# FPGA_IO.net
KiCad netlist of a schematic drawn in Altium Designer
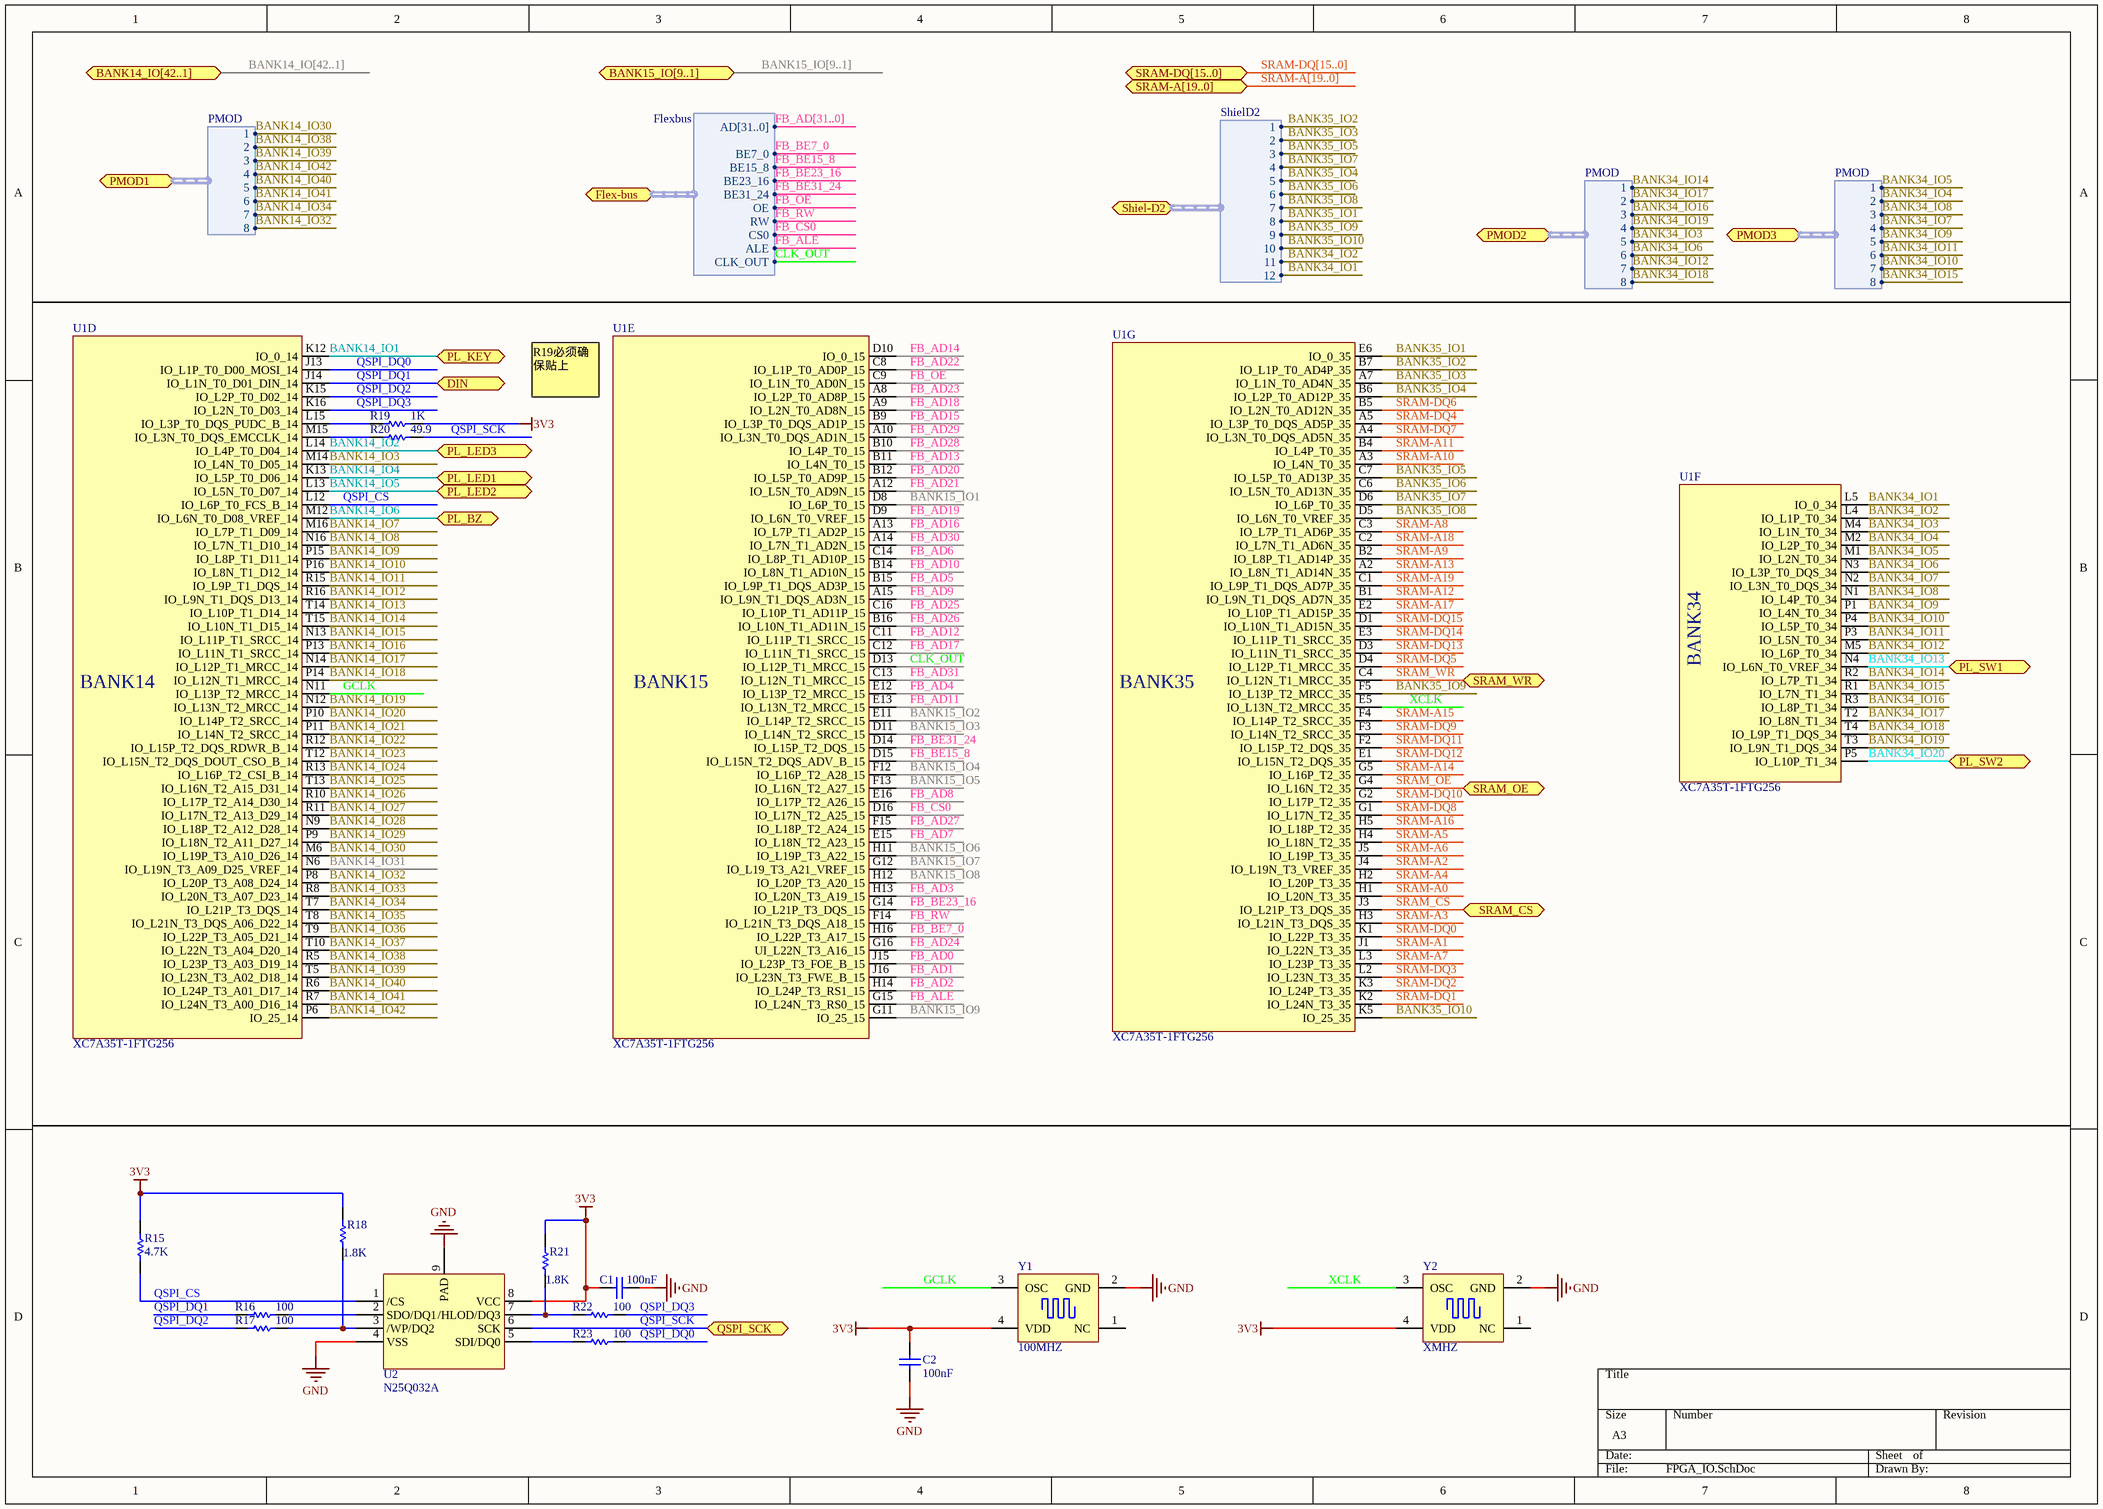
[diagram p0: FPGA_IO.SchDoc]

(export (version "E")
  (design (tool "Eeschema 10.0.6"))
  (components
    (comp (ref "C1")
      (value "100nF")
      (footprint "1608[0603]")
      (description "贴片电容")
      (fields (field (name "Comment") "Cap") (field (name "PUBLISHER") "Altium Limited"))
      (libsource (lib "Sparks") (part "Cap"))
    )
    (comp (ref "C2")
      (value "100nF")
      (footprint "1608[0603]")
      (description "贴片电容")
      (fields (field (name "Comment") "Cap") (field (name "PUBLISHER") "Altium Limited"))
      (libsource (lib "Sparks") (part "Cap"))
    )
    (comp (ref "R15")
      (value "4.7K")
      (footprint "1608[0603]")
      (description "贴片电阻")
      (fields (field (name "Comment") "Res") (field (name "PUBLISHER") "Altium Limited"))
      (libsource (lib "Sparks") (part "Res"))
    )
    (comp (ref "R16")
      (value "100")
      (footprint "1608[0603]")
      (description "贴片电阻")
      (fields (field (name "Comment") "Res") (field (name "PUBLISHER") "Altium Limited"))
      (libsource (lib "Sparks") (part "Res"))
    )
    (comp (ref "R17")
      (value "100")
      (footprint "1608[0603]")
      (description "贴片电阻")
      (fields (field (name "Comment") "Res") (field (name "PUBLISHER") "Altium Limited"))
      (libsource (lib "Sparks") (part "Res"))
    )
    (comp (ref "R18")
      (value "1.8K")
      (footprint "1608[0603]")
      (description "贴片电阻")
      (fields (field (name "Comment") "Res") (field (name "PUBLISHER") "Altium Limited"))
      (libsource (lib "Sparks") (part "Res"))
    )
    (comp (ref "R19")
      (value "1K")
      (footprint "1608[0603]")
      (description "贴片电阻")
      (fields (field (name "Comment") "Res") (field (name "PUBLISHER") "Altium Limited"))
      (libsource (lib "Sparks") (part "Res"))
    )
    (comp (ref "R20")
      (value "49.9")
      (footprint "R2012")
      (description "贴片电阻")
      (fields (field (name "Comment") "Res") (field (name "PUBLISHER") "Altium Limited"))
      (libsource (lib "Sparks") (part "Res"))
    )
    (comp (ref "R21")
      (value "1.8K")
      (footprint "1608[0603]")
      (description "贴片电阻")
      (fields (field (name "Comment") "Res") (field (name "PUBLISHER") "Altium Limited"))
      (libsource (lib "Sparks") (part "Res"))
    )
    (comp (ref "R22")
      (value "100")
      (footprint "1608[0603]")
      (description "贴片电阻")
      (fields (field (name "Comment") "Res") (field (name "PUBLISHER") "Altium Limited"))
      (libsource (lib "Sparks") (part "Res"))
    )
    (comp (ref "R23")
      (value "100")
      (footprint "R2012")
      (description "贴片电阻")
      (fields (field (name "Comment") "Res") (field (name "PUBLISHER") "Altium Limited"))
      (libsource (lib "Sparks") (part "Res"))
    )
    (comp (ref "U1")
      (value "XC7A35T-1FTG256")
      (footprint "BGA100P9X9-81A")
      (libsource (lib "Schlib") (part "XC7A35T-1FTG256"))
    )
    (comp (ref "U2")
      (value "N25Q032A")
      (footprint "QFN127P500X600X100_HS-9N")
      (libsource (lib "2号库") (part "N25Q032A"))
    )
    (comp (ref "Y1") (value "100MHZ") (footprint "XTAL7_3225") (libsource (lib "K60-V4.0") (part "XTAL1")))
    (comp (ref "Y2") (value "XMHZ") (footprint "XTAL7_3225") (libsource (lib "K60-V4.0") (part "XTAL1")))
  )
  (nets
    (net (code "4") (name "/BANK14_IO1") (class "Default")
      (node (ref "U1") (pin "K12") (pinfunction "IO_0_14_K12") (pintype "passive"))
    )
    (net (code "5") (name "/BANK14_IO2") (class "Default")
      (node (ref "U1") (pin "L14") (pinfunction "IO_L4P_T0_D04_14_L14") (pintype "passive"))
    )
    (net (code "6") (name "/BANK14_IO3") (class "Default")
      (node (ref "U1") (pin "M14") (pinfunction "IO_L4N_T0_D05_14_M14") (pintype "passive"))
    )
    (net (code "7") (name "/BANK14_IO4") (class "Default")
      (node (ref "U1") (pin "K13") (pinfunction "IO_L5P_T0_D06_14_K13") (pintype "passive"))
    )
    (net (code "8") (name "/BANK14_IO5") (class "Default")
      (node (ref "U1") (pin "L13") (pinfunction "IO_L5N_T0_D07_14_L13") (pintype "passive"))
    )
    (net (code "9") (name "/BANK14_IO6") (class "Default")
      (node (ref "U1") (pin "M12") (pinfunction "IO_L6N_T0_D08_VREF_14_M12") (pintype "passive"))
    )
    (net (code "10") (name "/BANK14_IO7") (class "Default")
      (node (ref "U1") (pin "M16") (pinfunction "IO_L7P_T1_D09_14_M16") (pintype "passive"))
    )
    (net (code "11") (name "/BANK14_IO8") (class "Default")
      (node (ref "U1") (pin "N16") (pinfunction "IO_L7N_T1_D10_14_N16") (pintype "passive"))
    )
    (net (code "12") (name "/BANK14_IO9") (class "Default")
      (node (ref "U1") (pin "P15") (pinfunction "IO_L8P_T1_D11_14_P15") (pintype "passive"))
    )
    (net (code "13") (name "/BANK14_IO10") (class "Default")
      (node (ref "U1") (pin "P16") (pinfunction "IO_L8N_T1_D12_14_P16") (pintype "passive"))
    )
    (net (code "14") (name "/BANK14_IO11") (class "Default")
      (node (ref "U1") (pin "R15") (pinfunction "IO_L9P_T1_DQS_14_R15") (pintype "passive"))
    )
    (net (code "15") (name "/BANK14_IO12") (class "Default")
      (node (ref "U1") (pin "R16") (pinfunction "IO_L9N_T1_DQS_D13_14_R16") (pintype "passive"))
    )
    (net (code "16") (name "/BANK14_IO13") (class "Default")
      (node (ref "U1") (pin "T14") (pinfunction "IO_L10P_T1_D14_14_T14") (pintype "passive"))
    )
    (net (code "17") (name "/BANK14_IO14") (class "Default")
      (node (ref "U1") (pin "T15") (pinfunction "IO_L10N_T1_D15_14_T15") (pintype "passive"))
    )
    (net (code "18") (name "/BANK14_IO15") (class "Default")
      (node (ref "U1") (pin "N13") (pinfunction "IO_L11P_T1_SRCC_14_N13") (pintype "passive"))
    )
    (net (code "19") (name "/BANK14_IO16") (class "Default")
      (node (ref "U1") (pin "P13") (pinfunction "IO_L11N_T1_SRCC_14_P13") (pintype "passive"))
    )
    (net (code "20") (name "/BANK14_IO17") (class "Default")
      (node (ref "U1") (pin "N14") (pinfunction "IO_L12P_T1_MRCC_14_N14") (pintype "passive"))
    )
    (net (code "21") (name "/BANK14_IO18") (class "Default")
      (node (ref "U1") (pin "P14") (pinfunction "IO_L12N_T1_MRCC_14_P14") (pintype "passive"))
    )
    (net (code "22") (name "/BANK14_IO19") (class "Default")
      (node (ref "U1") (pin "N12") (pinfunction "IO_L13N_T2_MRCC_14_N12") (pintype "passive"))
    )
    (net (code "23") (name "/BANK14_IO20") (class "Default")
      (node (ref "U1") (pin "P10") (pinfunction "IO_L14P_T2_SRCC_14_P10") (pintype "passive"))
    )
    (net (code "24") (name "/BANK14_IO21") (class "Default")
      (node (ref "U1") (pin "P11") (pinfunction "IO_L14N_T2_SRCC_14_P11") (pintype "passive"))
    )
    (net (code "25") (name "/BANK14_IO22") (class "Default")
      (node (ref "U1") (pin "R12") (pinfunction "IO_L15P_T2_DQS_RDWR_B_14_R12") (pintype "passive"))
    )
    (net (code "26") (name "/BANK14_IO23") (class "Default")
      (node (ref "U1") (pin "T12") (pinfunction "IO_L15N_T2_DQS_DOUT_CSO_B_14_T12") (pintype "passive"))
    )
    (net (code "27") (name "/BANK14_IO24") (class "Default")
      (node (ref "U1") (pin "R13") (pinfunction "IO_L16P_T2_CSI_B_14_R13") (pintype "passive"))
    )
    (net (code "28") (name "/BANK14_IO25") (class "Default")
      (node (ref "U1") (pin "T13") (pinfunction "IO_L16N_T2_A15_D31_14_T13") (pintype "passive"))
    )
    (net (code "29") (name "/BANK14_IO26") (class "Default")
      (node (ref "U1") (pin "R10") (pinfunction "IO_L17P_T2_A14_D30_14_R10") (pintype "passive"))
    )
    (net (code "30") (name "/BANK14_IO27") (class "Default")
      (node (ref "U1") (pin "R11") (pinfunction "IO_L17N_T2_A13_D29_14_R11") (pintype "passive"))
    )
    (net (code "31") (name "/BANK14_IO28") (class "Default")
      (node (ref "U1") (pin "N9") (pinfunction "IO_L18P_T2_A12_D28_14_N9") (pintype "passive"))
    )
    (net (code "32") (name "/BANK14_IO29") (class "Default")
      (node (ref "U1") (pin "P9") (pinfunction "IO_L18N_T2_A11_D27_14_P9") (pintype "passive"))
    )
    (net (code "33") (name "/BANK14_IO30") (class "Default")
      (node (ref "U1") (pin "M6") (pinfunction "IO_L19P_T3_A10_D26_14_M6") (pintype "passive"))
    )
    (net (code "34") (name "/BANK14_IO31") (class "Default")
      (node (ref "U1") (pin "N6") (pinfunction "IO_L19N_T3_A09_D25_VREF_14_N6") (pintype "passive"))
    )
    (net (code "35") (name "/BANK14_IO32") (class "Default")
      (node (ref "U1") (pin "P8") (pinfunction "IO_L20P_T3_A08_D24_14_P8") (pintype "passive"))
    )
    (net (code "36") (name "/BANK14_IO33") (class "Default")
      (node (ref "U1") (pin "R8") (pinfunction "IO_L20N_T3_A07_D23_14_R8") (pintype "passive"))
    )
    (net (code "37") (name "/BANK14_IO34") (class "Default")
      (node (ref "U1") (pin "T7") (pinfunction "IO_L21P_T3_DQS_14_T7") (pintype "passive"))
    )
    (net (code "38") (name "/BANK14_IO35") (class "Default")
      (node (ref "U1") (pin "T8") (pinfunction "IO_L21N_T3_DQS_A06_D22_14_T8") (pintype "passive"))
    )
    (net (code "39") (name "/BANK14_IO36") (class "Default")
      (node (ref "U1") (pin "T9") (pinfunction "IO_L22P_T3_A05_D21_14_T9") (pintype "passive"))
    )
    (net (code "40") (name "/BANK14_IO37") (class "Default")
      (node (ref "U1") (pin "T10") (pinfunction "IO_L22N_T3_A04_D20_14_T10") (pintype "passive"))
    )
    (net (code "41") (name "/BANK14_IO38") (class "Default")
      (node (ref "U1") (pin "R5") (pinfunction "IO_L23P_T3_A03_D19_14_R5") (pintype "passive"))
    )
    (net (code "42") (name "/BANK14_IO39") (class "Default")
      (node (ref "U1") (pin "T5") (pinfunction "IO_L23N_T3_A02_D18_14_T5") (pintype "passive"))
    )
    (net (code "43") (name "/BANK14_IO40") (class "Default")
      (node (ref "U1") (pin "R6") (pinfunction "IO_L24P_T3_A01_D17_14_R6") (pintype "passive"))
    )
    (net (code "44") (name "/BANK14_IO41") (class "Default")
      (node (ref "U1") (pin "R7") (pinfunction "IO_L24N_T3_A00_D16_14_R7") (pintype "passive"))
    )
    (net (code "45") (name "/BANK14_IO42") (class "Default")
      (node (ref "U1") (pin "P6") (pinfunction "IO_25_14_P6") (pintype "passive"))
    )
    (net (code "47") (name "/BANK15_IO1") (class "Default")
      (node (ref "U1") (pin "D8") (pinfunction "IO_L6P_T0_15_D8") (pintype "passive"))
    )
    (net (code "48") (name "/BANK15_IO2") (class "Default")
      (node (ref "U1") (pin "E11") (pinfunction "IO_L14P_T2_SRCC_15_E11") (pintype "passive"))
    )
    (net (code "49") (name "/BANK15_IO3") (class "Default")
      (node (ref "U1") (pin "D11") (pinfunction "IO_L14N_T2_SRCC_15_D11") (pintype "passive"))
    )
    (net (code "50") (name "/BANK15_IO4") (class "Default")
      (node (ref "U1") (pin "F12") (pinfunction "IO_L16P_T2_A28_15_F12") (pintype "passive"))
    )
    (net (code "51") (name "/BANK15_IO5") (class "Default")
      (node (ref "U1") (pin "F13") (pinfunction "IO_L16N_T2_A27_15_F13") (pintype "passive"))
    )
    (net (code "52") (name "/BANK15_IO6") (class "Default")
      (node (ref "U1") (pin "H11") (pinfunction "IO_L19P_T3_A22_15_H11") (pintype "passive"))
    )
    (net (code "53") (name "/BANK15_IO7") (class "Default")
      (node (ref "U1") (pin "G12") (pinfunction "IO_L19_T3_A21_VREF_15_G12") (pintype "passive"))
    )
    (net (code "54") (name "/BANK15_IO8") (class "Default")
      (node (ref "U1") (pin "H12") (pinfunction "IO_L20P_T3_A20_15_H12") (pintype "passive"))
    )
    (net (code "55") (name "/BANK15_IO9") (class "Default")
      (node (ref "U1") (pin "G11") (pinfunction "IO_25_15_G11") (pintype "passive"))
    )
    (net (code "57") (name "/BANK34_IO1") (class "Default")
      (node (ref "U1") (pin "L5") (pinfunction "IO_0_34_L5") (pintype "passive"))
    )
    (net (code "58") (name "/BANK34_IO2") (class "Default")
      (node (ref "U1") (pin "L4") (pinfunction "IO_L1P_T0_34_L4") (pintype "passive"))
    )
    (net (code "59") (name "/BANK34_IO3") (class "Default")
      (node (ref "U1") (pin "M4") (pinfunction "IO_L1N_T0_34_M4") (pintype "passive"))
    )
    (net (code "60") (name "/BANK34_IO4") (class "Default")
      (node (ref "U1") (pin "M2") (pinfunction "IO_L2P_T0_34_M2") (pintype "passive"))
    )
    (net (code "61") (name "/BANK34_IO5") (class "Default")
      (node (ref "U1") (pin "M1") (pinfunction "IO_L2N_T0_34_M1") (pintype "passive"))
    )
    (net (code "62") (name "/BANK34_IO6") (class "Default")
      (node (ref "U1") (pin "N3") (pinfunction "IO_L3P_T0_DQS_34_N3") (pintype "passive"))
    )
    (net (code "63") (name "/BANK34_IO7") (class "Default")
      (node (ref "U1") (pin "N2") (pinfunction "IO_L3N_T0_DQS_34_N2") (pintype "passive"))
    )
    (net (code "64") (name "/BANK34_IO8") (class "Default")
      (node (ref "U1") (pin "N1") (pinfunction "IO_L4P_T0_34_N1") (pintype "passive"))
    )
    (net (code "65") (name "/BANK34_IO9") (class "Default")
      (node (ref "U1") (pin "P1") (pinfunction "IO_L4N_T0_34_P1") (pintype "passive"))
    )
    (net (code "66") (name "/BANK34_IO10") (class "Default")
      (node (ref "U1") (pin "P4") (pinfunction "IO_L5P_T0_34_P4") (pintype "passive"))
    )
    (net (code "67") (name "/BANK34_IO11") (class "Default")
      (node (ref "U1") (pin "P3") (pinfunction "IO_L5N_T0_34_P3") (pintype "passive"))
    )
    (net (code "68") (name "/BANK34_IO12") (class "Default")
      (node (ref "U1") (pin "M5") (pinfunction "IO_L6P_T0_34_M5") (pintype "passive"))
    )
    (net (code "69") (name "/BANK34_IO13") (class "Default")
      (node (ref "U1") (pin "N4") (pinfunction "IO_L6N_T0_VREF_34_N4") (pintype "passive"))
    )
    (net (code "70") (name "/BANK34_IO14") (class "Default")
      (node (ref "U1") (pin "R2") (pinfunction "IO_L7P_T1_34_R2") (pintype "passive"))
    )
    (net (code "71") (name "/BANK34_IO15") (class "Default")
      (node (ref "U1") (pin "R1") (pinfunction "IO_L7N_T1_34_R1") (pintype "passive"))
    )
    (net (code "72") (name "/BANK34_IO16") (class "Default")
      (node (ref "U1") (pin "R3") (pinfunction "IO_L8P_T1_34_R3") (pintype "passive"))
    )
    (net (code "73") (name "/BANK34_IO17") (class "Default")
      (node (ref "U1") (pin "T2") (pinfunction "IO_L8N_T1_34_T2") (pintype "passive"))
    )
    (net (code "74") (name "/BANK34_IO18") (class "Default")
      (node (ref "U1") (pin "T4") (pinfunction "IO_L9P_T1_DQS_34_T4") (pintype "passive"))
    )
    (net (code "75") (name "/BANK34_IO19") (class "Default")
      (node (ref "U1") (pin "T3") (pinfunction "IO_L9N_T1_DQS_34_T3") (pintype "passive"))
    )
    (net (code "76") (name "/BANK34_IO20") (class "Default")
      (node (ref "U1") (pin "P5") (pinfunction "IO_L10P_T1_34_P5") (pintype "passive"))
    )
    (net (code "77") (name "/BANK35_IO1") (class "Default")
      (node (ref "U1") (pin "E6") (pinfunction "IO_0_35_E6") (pintype "passive"))
    )
    (net (code "78") (name "/BANK35_IO2") (class "Default")
      (node (ref "U1") (pin "B7") (pinfunction "IO_L1P_T0_AD4P_35_B7") (pintype "passive"))
    )
    (net (code "79") (name "/BANK35_IO3") (class "Default")
      (node (ref "U1") (pin "A7") (pinfunction "IO_L1N_T0_AD4N_35_A7") (pintype "passive"))
    )
    (net (code "80") (name "/BANK35_IO4") (class "Default")
      (node (ref "U1") (pin "B6") (pinfunction "IO_L2P_T0_AD12P_35_B6") (pintype "passive"))
    )
    (net (code "81") (name "/BANK35_IO5") (class "Default")
      (node (ref "U1") (pin "C7") (pinfunction "IO_L5P_T0_AD13P_35_C7") (pintype "passive"))
    )
    (net (code "82") (name "/BANK35_IO6") (class "Default")
      (node (ref "U1") (pin "C6") (pinfunction "IO_L5N_T0_AD13N_35_C6") (pintype "passive"))
    )
    (net (code "83") (name "/BANK35_IO7") (class "Default")
      (node (ref "U1") (pin "D6") (pinfunction "IO_L6P_T0_35_D6") (pintype "passive"))
    )
    (net (code "84") (name "/BANK35_IO8") (class "Default")
      (node (ref "U1") (pin "D5") (pinfunction "IO_L6N_T0_VREF_35_D5") (pintype "passive"))
    )
    (net (code "85") (name "/BANK35_IO9") (class "Default")
      (node (ref "U1") (pin "F5") (pinfunction "IO_L13P_T2_MRCC_35_F5") (pintype "passive"))
    )
    (net (code "86") (name "/BANK35_IO10") (class "Default")
      (node (ref "U1") (pin "K5") (pinfunction "IO_25_35_K5") (pintype "passive"))
    )
    (net (code "87") (name "/CLK_OUT") (class "Default")
      (node (ref "U1") (pin "D13") (pinfunction "IO_L12P_T1_MRCC_15_D13") (pintype "passive"))
    )
    (net (code "88") (name "/FB_AD0") (class "Default")
      (node (ref "U1") (pin "J15") (pinfunction "IO_L23P_T3_FOE_B_15_J15") (pintype "passive"))
    )
    (net (code "89") (name "/FB_AD1") (class "Default")
      (node (ref "U1") (pin "J16") (pinfunction "IO_L23N_T3_FWE_B_15_J16") (pintype "passive"))
    )
    (net (code "90") (name "/FB_AD2") (class "Default")
      (node (ref "U1") (pin "H14") (pinfunction "IO_L24P_T3_RS1_15_H14") (pintype "passive"))
    )
    (net (code "91") (name "/FB_AD3") (class "Default")
      (node (ref "U1") (pin "H13") (pinfunction "IO_L20N_T3_A19_15_H13") (pintype "passive"))
    )
    (net (code "92") (name "/FB_AD4") (class "Default")
      (node (ref "U1") (pin "E12") (pinfunction "IO_L13P_T2_MRCC_15_E12") (pintype "passive"))
    )
    (net (code "93") (name "/FB_AD5") (class "Default")
      (node (ref "U1") (pin "B15") (pinfunction "IO_L9P_T1_DQS_AD3P_15_B15") (pintype "passive"))
    )
    (net (code "94") (name "/FB_AD6") (class "Default")
      (node (ref "U1") (pin "C14") (pinfunction "IO_L8P_T1_AD10P_15_C14") (pintype "passive"))
    )
    (net (code "95") (name "/FB_AD7") (class "Default")
      (node (ref "U1") (pin "E15") (pinfunction "IO_L18N_T2_A23_15_E15") (pintype "passive"))
    )
    (net (code "96") (name "/FB_AD8") (class "Default")
      (node (ref "U1") (pin "E16") (pinfunction "IO_L17P_T2_A26_15_E16") (pintype "passive"))
    )
    (net (code "97") (name "/FB_AD9") (class "Default")
      (node (ref "U1") (pin "A15") (pinfunction "IO_L9N_T1_DQS_AD3N_15_A15") (pintype "passive"))
    )
    (net (code "98") (name "/FB_AD10") (class "Default")
      (node (ref "U1") (pin "B14") (pinfunction "IO_L8N_T1_AD10N_15_B14") (pintype "passive"))
    )
    (net (code "99") (name "/FB_AD11") (class "Default")
      (node (ref "U1") (pin "E13") (pinfunction "IO_L13N_T2_MRCC_15_E13") (pintype "passive"))
    )
    (net (code "100") (name "/FB_AD12") (class "Default")
      (node (ref "U1") (pin "C11") (pinfunction "IO_L11P_T1_SRCC_15_C11") (pintype "passive"))
    )
    (net (code "101") (name "/FB_AD13") (class "Default")
      (node (ref "U1") (pin "B11") (pinfunction "IO_L4N_T0_15_B11") (pintype "passive"))
    )
    (net (code "102") (name "/FB_AD14") (class "Default")
      (node (ref "U1") (pin "D10") (pinfunction "IO_0_15_D10") (pintype "passive"))
    )
    (net (code "103") (name "/FB_AD15") (class "Default")
      (node (ref "U1") (pin "B9") (pinfunction "IO_L3P_T0_DQS_AD1P_15_B9") (pintype "passive"))
    )
    (net (code "104") (name "/FB_AD16") (class "Default")
      (node (ref "U1") (pin "A13") (pinfunction "IO_L7P_T1_AD2P_15_A13") (pintype "passive"))
    )
    (net (code "105") (name "/FB_AD17") (class "Default")
      (node (ref "U1") (pin "C12") (pinfunction "IO_L11N_T1_SRCC_15_C12") (pintype "passive"))
    )
    (net (code "106") (name "/FB_AD18") (class "Default")
      (node (ref "U1") (pin "A9") (pinfunction "IO_L2N_T0_AD8N_15_A9") (pintype "passive"))
    )
    (net (code "107") (name "/FB_AD19") (class "Default")
      (node (ref "U1") (pin "D9") (pinfunction "IO_L6N_T0_VREF_15_D9") (pintype "passive"))
    )
    (net (code "108") (name "/FB_AD20") (class "Default")
      (node (ref "U1") (pin "B12") (pinfunction "IO_L5P_T0_AD9P_15_B12") (pintype "passive"))
    )
    (net (code "109") (name "/FB_AD21") (class "Default")
      (node (ref "U1") (pin "A12") (pinfunction "IO_L5N_T0_AD9N_15_A12") (pintype "passive"))
    )
    (net (code "110") (name "/FB_AD22") (class "Default")
      (node (ref "U1") (pin "C8") (pinfunction "IO_L1P_T0_AD0P_15_C8") (pintype "passive"))
    )
    (net (code "111") (name "/FB_AD23") (class "Default")
      (node (ref "U1") (pin "A8") (pinfunction "IO_L2P_T0_AD8P_15_A8") (pintype "passive"))
    )
    (net (code "112") (name "/FB_AD24") (class "Default")
      (node (ref "U1") (pin "G16") (pinfunction "UI_L22N_T3_A16_15_G16") (pintype "passive"))
    )
    (net (code "113") (name "/FB_AD25") (class "Default")
      (node (ref "U1") (pin "C16") (pinfunction "IO_L10P_T1_AD11P_15_C16") (pintype "passive"))
    )
    (net (code "114") (name "/FB_AD26") (class "Default")
      (node (ref "U1") (pin "B16") (pinfunction "IO_L10N_T1_AD11N_15_B16") (pintype "passive"))
    )
    (net (code "115") (name "/FB_AD27") (class "Default")
      (node (ref "U1") (pin "F15") (pinfunction "IO_L18P_T2_A24_15_F15") (pintype "passive"))
    )
    (net (code "116") (name "/FB_AD28") (class "Default")
      (node (ref "U1") (pin "B10") (pinfunction "IO_L4P_T0_15_B10") (pintype "passive"))
    )
    (net (code "117") (name "/FB_AD29") (class "Default")
      (node (ref "U1") (pin "A10") (pinfunction "IO_L3N_T0_DQS_AD1N_15_A10") (pintype "passive"))
    )
    (net (code "118") (name "/FB_AD30") (class "Default")
      (node (ref "U1") (pin "A14") (pinfunction "IO_L7N_T1_AD2N_15_A14") (pintype "passive"))
    )
    (net (code "119") (name "/FB_AD31") (class "Default")
      (node (ref "U1") (pin "C13") (pinfunction "IO_L12N_T1_MRCC_15_C13") (pintype "passive"))
    )
    (net (code "120") (name "/FB_ALE") (class "Default")
      (node (ref "U1") (pin "G15") (pinfunction "IO_L24N_T3_RS0_15_G15") (pintype "passive"))
    )
    (net (code "121") (name "/FB_BE7_0") (class "Default")
      (node (ref "U1") (pin "H16") (pinfunction "IO_L22P_T3_A17_15_H16") (pintype "passive"))
    )
    (net (code "122") (name "/FB_BE15_8") (class "Default")
      (node (ref "U1") (pin "D15") (pinfunction "IO_L15N_T2_DQS_ADV_B_15_D15") (pintype "passive"))
    )
    (net (code "123") (name "/FB_BE23_16") (class "Default")
      (node (ref "U1") (pin "G14") (pinfunction "IO_L21P_T3_DQS_15_G14") (pintype "passive"))
    )
    (net (code "124") (name "/FB_BE31_24") (class "Default")
      (node (ref "U1") (pin "D14") (pinfunction "IO_L15P_T2_DQS_15_D14") (pintype "passive"))
    )
    (net (code "125") (name "/FB_CS0") (class "Default")
      (node (ref "U1") (pin "D16") (pinfunction "IO_L17N_T2_A25_15_D16") (pintype "passive"))
    )
    (net (code "126") (name "/FB_OE") (class "Default")
      (node (ref "U1") (pin "C9") (pinfunction "IO_L1N_T0_AD0N_15_C9") (pintype "passive"))
    )
    (net (code "127") (name "/FB_RW") (class "Default")
      (node (ref "U1") (pin "F14") (pinfunction "IO_L21N_T3_DQS_A18_15_F14") (pintype "passive"))
    )
    (net (code "129") (name "/GCLK") (class "Default")
      (node (ref "U1") (pin "N11") (pinfunction "IO_L13P_T2_MRCC_14_N11") (pintype "passive"))
      (node (ref "Y1") (pin "3") (pinfunction "OSC_3") (pintype "passive"))
    )
    (net (code "130") (name "/QSPI_CS") (class "Default")
      (node (ref "R15") (pin "2") (pinfunction "2_2") (pintype "passive"))
      (node (ref "U1") (pin "L12") (pinfunction "IO_L6P_T0_FCS_B_14_L12") (pintype "passive"))
      (node (ref "U2") (pin "1") (pinfunction "/CS_1") (pintype "passive"))
    )
    (net (code "131") (name "/QSPI_DQ0") (class "Default")
      (node (ref "R23") (pin "1") (pinfunction "1_1") (pintype "passive"))
      (node (ref "U1") (pin "J13") (pinfunction "IO_L1P_T0_D00_MOSI_14_J13") (pintype "passive"))
    )
    (net (code "132") (name "/QSPI_DQ1") (class "Default")
      (node (ref "R16") (pin "2") (pinfunction "2_2") (pintype "passive"))
      (node (ref "U1") (pin "J14") (pinfunction "IO_L1N_T0_D01_DIN_14_J14") (pintype "passive"))
    )
    (net (code "133") (name "/QSPI_DQ2") (class "Default")
      (node (ref "R17") (pin "2") (pinfunction "2_2") (pintype "passive"))
      (node (ref "U1") (pin "K15") (pinfunction "IO_L2P_T0_D02_14_K15") (pintype "passive"))
    )
    (net (code "134") (name "/QSPI_DQ3") (class "Default")
      (node (ref "R22") (pin "1") (pinfunction "1_1") (pintype "passive"))
      (node (ref "U1") (pin "K16") (pinfunction "IO_L2N_T0_D03_14_K16") (pintype "passive"))
    )
    (net (code "135") (name "/QSPI_SCK") (class "Default")
      (node (ref "R20") (pin "1") (pinfunction "1_1") (pintype "passive"))
      (node (ref "U2") (pin "6") (pinfunction "SCK_6") (pintype "passive"))
    )
    (net (code "136") (name "/SRAM-A0") (class "Default")
      (node (ref "U1") (pin "H1") (pinfunction "IO_L20N_T3_35_H1") (pintype "passive"))
    )
    (net (code "137") (name "/SRAM-A1") (class "Default")
      (node (ref "U1") (pin "J1") (pinfunction "IO_L22N_T3_35_J1") (pintype "passive"))
    )
    (net (code "138") (name "/SRAM-A2") (class "Default")
      (node (ref "U1") (pin "J4") (pinfunction "IO_L19N_T3_VREF_35_J4") (pintype "passive"))
    )
    (net (code "139") (name "/SRAM-A3") (class "Default")
      (node (ref "U1") (pin "H3") (pinfunction "IO_L21N_T3_DQS_35_H3") (pintype "passive"))
    )
    (net (code "140") (name "/SRAM-A4") (class "Default")
      (node (ref "U1") (pin "H2") (pinfunction "IO_L20P_T3_35_H2") (pintype "passive"))
    )
    (net (code "141") (name "/SRAM-A5") (class "Default")
      (node (ref "U1") (pin "H4") (pinfunction "IO_L18N_T2_35_H4") (pintype "passive"))
    )
    (net (code "142") (name "/SRAM-A6") (class "Default")
      (node (ref "U1") (pin "J5") (pinfunction "IO_L19P_T3_35_J5") (pintype "passive"))
    )
    (net (code "143") (name "/SRAM-A7") (class "Default")
      (node (ref "U1") (pin "L3") (pinfunction "IO_L23P_T3_35_L3") (pintype "passive"))
    )
    (net (code "144") (name "/SRAM-A8") (class "Default")
      (node (ref "U1") (pin "C3") (pinfunction "IO_L7P_T1_AD6P_35_C3") (pintype "passive"))
    )
    (net (code "145") (name "/SRAM-A9") (class "Default")
      (node (ref "U1") (pin "B2") (pinfunction "IO_L8P_T1_AD14P_35_B2") (pintype "passive"))
    )
    (net (code "146") (name "/SRAM-A10") (class "Default")
      (node (ref "U1") (pin "A3") (pinfunction "IO_L4N_T0_35_A3") (pintype "passive"))
    )
    (net (code "147") (name "/SRAM-A11") (class "Default")
      (node (ref "U1") (pin "B4") (pinfunction "IO_L4P_T0_35_B4") (pintype "passive"))
    )
    (net (code "148") (name "/SRAM-A12") (class "Default")
      (node (ref "U1") (pin "B1") (pinfunction "IO_L9N_T1_DQS_AD7N_35_B1") (pintype "passive"))
    )
    (net (code "149") (name "/SRAM-A13") (class "Default")
      (node (ref "U1") (pin "A2") (pinfunction "IO_L8N_T1_AD14N_35_A2") (pintype "passive"))
    )
    (net (code "150") (name "/SRAM-A14") (class "Default")
      (node (ref "U1") (pin "G5") (pinfunction "IO_L16P_T2_35_G5") (pintype "passive"))
    )
    (net (code "151") (name "/SRAM-A15") (class "Default")
      (node (ref "U1") (pin "F4") (pinfunction "IO_L14P_T2_SRCC_35_F4") (pintype "passive"))
    )
    (net (code "152") (name "/SRAM-A16") (class "Default")
      (node (ref "U1") (pin "H5") (pinfunction "IO_L18P_T2_35_H5") (pintype "passive"))
    )
    (net (code "153") (name "/SRAM-A17") (class "Default")
      (node (ref "U1") (pin "E2") (pinfunction "IO_L10P_T1_AD15P_35_E2") (pintype "passive"))
    )
    (net (code "154") (name "/SRAM-A18") (class "Default")
      (node (ref "U1") (pin "C2") (pinfunction "IO_L7N_T1_AD6N_35_C2") (pintype "passive"))
    )
    (net (code "155") (name "/SRAM-A19") (class "Default")
      (node (ref "U1") (pin "C1") (pinfunction "IO_L9P_T1_DQS_AD7P_35_C1") (pintype "passive"))
    )
    (net (code "157") (name "/SRAM-DQ0") (class "Default")
      (node (ref "U1") (pin "K1") (pinfunction "IO_L22P_T3_35_K1") (pintype "passive"))
    )
    (net (code "158") (name "/SRAM-DQ1") (class "Default")
      (node (ref "U1") (pin "K2") (pinfunction "IO_L24N_T3_35_K2") (pintype "passive"))
    )
    (net (code "159") (name "/SRAM-DQ2") (class "Default")
      (node (ref "U1") (pin "K3") (pinfunction "IO_L24P_T3_35_K3") (pintype "passive"))
    )
    (net (code "160") (name "/SRAM-DQ3") (class "Default")
      (node (ref "U1") (pin "L2") (pinfunction "IO_L23N_T3_35_L2") (pintype "passive"))
    )
    (net (code "161") (name "/SRAM-DQ4") (class "Default")
      (node (ref "U1") (pin "A5") (pinfunction "IO_L3P_T0_DQS_AD5P_35_A5") (pintype "passive"))
    )
    (net (code "162") (name "/SRAM-DQ5") (class "Default")
      (node (ref "U1") (pin "D4") (pinfunction "IO_L12P_T1_MRCC_35_D4") (pintype "passive"))
    )
    (net (code "163") (name "/SRAM-DQ6") (class "Default")
      (node (ref "U1") (pin "B5") (pinfunction "IO_L2N_T0_AD12N_35_B5") (pintype "passive"))
    )
    (net (code "164") (name "/SRAM-DQ7") (class "Default")
      (node (ref "U1") (pin "A4") (pinfunction "IO_L3N_T0_DQS_AD5N_35_A4") (pintype "passive"))
    )
    (net (code "165") (name "/SRAM-DQ8") (class "Default")
      (node (ref "U1") (pin "G1") (pinfunction "IO_L17N_T2_35_G1") (pintype "passive"))
    )
    (net (code "166") (name "/SRAM-DQ9") (class "Default")
      (node (ref "U1") (pin "F3") (pinfunction "IO_L14N_T2_SRCC_35_F3") (pintype "passive"))
    )
    (net (code "167") (name "/SRAM-DQ10") (class "Default")
      (node (ref "U1") (pin "G2") (pinfunction "IO_L17P_T2_35_G2") (pintype "passive"))
    )
    (net (code "168") (name "/SRAM-DQ11") (class "Default")
      (node (ref "U1") (pin "F2") (pinfunction "IO_L15P_T2_DQS_35_F2") (pintype "passive"))
    )
    (net (code "169") (name "/SRAM-DQ12") (class "Default")
      (node (ref "U1") (pin "E1") (pinfunction "IO_L15N_T2_DQS_35_E1") (pintype "passive"))
    )
    (net (code "170") (name "/SRAM-DQ13") (class "Default")
      (node (ref "U1") (pin "D3") (pinfunction "IO_L11N_T1_SRCC_35_D3") (pintype "passive"))
    )
    (net (code "171") (name "/SRAM-DQ14") (class "Default")
      (node (ref "U1") (pin "E3") (pinfunction "IO_L11P_T1_SRCC_35_E3") (pintype "passive"))
    )
    (net (code "172") (name "/SRAM-DQ15") (class "Default")
      (node (ref "U1") (pin "D1") (pinfunction "IO_L10N_T1_AD15N_35_D1") (pintype "passive"))
    )
    (net (code "174") (name "/SRAM_CS") (class "Default")
      (node (ref "U1") (pin "J3") (pinfunction "IO_L21P_T3_DQS_35_J3") (pintype "passive"))
    )
    (net (code "175") (name "/SRAM_OE") (class "Default")
      (node (ref "U1") (pin "G4") (pinfunction "IO_L16N_T2_35_G4") (pintype "passive"))
    )
    (net (code "176") (name "/SRAM_WR") (class "Default")
      (node (ref "U1") (pin "C4") (pinfunction "IO_L12N_T1_MRCC_35_C4") (pintype "passive"))
    )
    (net (code "177") (name "/XCLK") (class "Default")
      (node (ref "U1") (pin "E5") (pinfunction "IO_L13N_T2_MRCC_35_E5") (pintype "passive"))
      (node (ref "Y2") (pin "3") (pinfunction "OSC_3") (pintype "passive"))
    )
    (net (code "181") (name "3V3") (class "Default")
      (node (ref "C1") (pin "1") (pinfunction "1_1") (pintype "passive"))
      (node (ref "C2") (pin "2") (pinfunction "2_2") (pintype "passive"))
      (node (ref "R15") (pin "1") (pinfunction "1_1") (pintype "passive"))
      (node (ref "R18") (pin "1") (pinfunction "1_1") (pintype "passive"))
      (node (ref "R19") (pin "1") (pinfunction "1_1") (pintype "passive"))
      (node (ref "R21") (pin "1") (pinfunction "1_1") (pintype "passive"))
      (node (ref "U2") (pin "8") (pinfunction "VCC_8") (pintype "passive"))
      (node (ref "Y1") (pin "4") (pinfunction "VDD_4") (pintype "passive"))
      (node (ref "Y2") (pin "4") (pinfunction "VDD_4") (pintype "passive"))
    )
    (net (code "182") (name "GND") (class "Default")
      (node (ref "C1") (pin "2") (pinfunction "2_2") (pintype "passive"))
      (node (ref "C2") (pin "1") (pinfunction "1_1") (pintype "passive"))
      (node (ref "U2") (pin "4") (pinfunction "VSS_4") (pintype "passive"))
      (node (ref "U2") (pin "9") (pinfunction "PAD_9") (pintype "passive"))
      (node (ref "Y1") (pin "2") (pinfunction "GND_2") (pintype "passive"))
      (node (ref "Y2") (pin "2") (pinfunction "GND_2") (pintype "passive"))
    )
    (net (code "183") (name "Net-(U1D-IO_L3N_T0_DQS_EMCCLK_14)") (class "Default")
      (node (ref "R20") (pin "2") (pinfunction "2_2") (pintype "passive"))
      (node (ref "U1") (pin "M15") (pinfunction "IO_L3N_T0_DQS_EMCCLK_14_M15") (pintype "passive"))
    )
    (net (code "184") (name "Net-(U1D-IO_L3P_T0_DQS_PUDC_B_14)") (class "Default")
      (node (ref "R19") (pin "2") (pinfunction "2_2") (pintype "passive"))
      (node (ref "U1") (pin "L15") (pinfunction "IO_L3P_T0_DQS_PUDC_B_14_L15") (pintype "passive"))
    )
    (net (code "185") (name "Net-(U2-SDI{slash}DQ0)") (class "Default")
      (node (ref "R23") (pin "2") (pinfunction "2_2") (pintype "passive"))
      (node (ref "U2") (pin "5") (pinfunction "SDI/DQ0_5") (pintype "passive"))
    )
    (net (code "186") (name "Net-(U2-SDO{slash}DQ1)") (class "Default")
      (node (ref "R16") (pin "1") (pinfunction "1_1") (pintype "passive"))
      (node (ref "U2") (pin "2") (pinfunction "SDO/DQ1_2") (pintype "passive"))
    )
    (net (code "187") (name "Net-(U2-{slash}HLOD{slash}DQ3)") (class "Default")
      (node (ref "R21") (pin "2") (pinfunction "2_2") (pintype "passive"))
      (node (ref "R22") (pin "2") (pinfunction "2_2") (pintype "passive"))
      (node (ref "U2") (pin "7") (pinfunction "/HLOD/DQ3_7") (pintype "passive"))
    )
    (net (code "188") (name "Net-(U2-{slash}WP{slash}DQ2)") (class "Default")
      (node (ref "R17") (pin "1") (pinfunction "1_1") (pintype "passive"))
      (node (ref "R18") (pin "2") (pinfunction "2_2") (pintype "passive"))
      (node (ref "U2") (pin "3") (pinfunction "/WP/DQ2_3") (pintype "passive"))
    )
    (net (code "189") (name "unconnected-(Y1-NC-Pad1)") (class "Default")
      (node (ref "Y1") (pin "1") (pinfunction "NC_1") (pintype "passive"))
    )
    (net (code "190") (name "unconnected-(Y2-NC-Pad1)") (class "Default")
      (node (ref "Y2") (pin "1") (pinfunction "NC_1") (pintype "passive"))
    )
  )
)
